# board__tzen.net
KiCad netlist of a schematic drawn in EAGLE
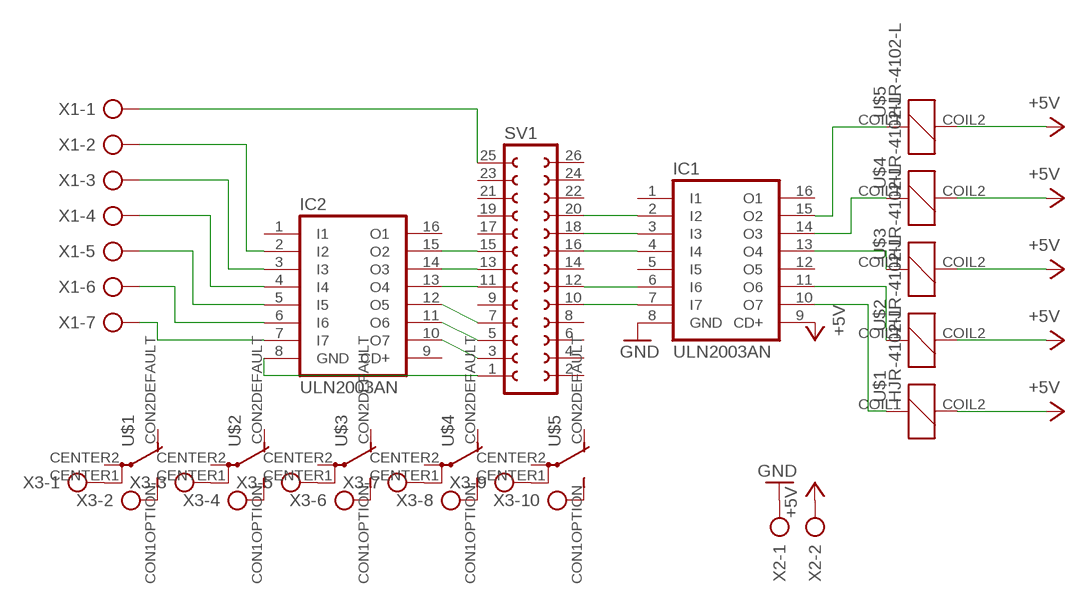
[diagram p0: schematic, sheet 1]

(export (version "E")
  (design (tool "Eeschema 10.0.6"))
  (components
    (comp (ref "IC1")
      (value "ULN2003AN")
      (footprint "eagle-import:DIL16")
      (libsource (lib "eagle-import") (part "ULN2003AN"))
    )
    (comp (ref "IC2")
      (value "ULN2003AN")
      (footprint "eagle-import:DIL16")
      (libsource (lib "eagle-import") (part "ULN2003AN"))
    )
    (comp (ref "SV1")
      (value "FE13-2")
      (footprint "eagle-import:FE13-2")
      (libsource (lib "eagle-import") (part "FE13-2"))
    )
    (comp (ref "U$1")
      (value "HJR-4102-L")
      (footprint "eagle-import:HJR4102")
      (libsource (lib "eagle-import") (part "HJR-4102-L"))
    )
    (comp (ref "U$2")
      (value "HJR-4102-L")
      (footprint "eagle-import:HJR4102")
      (libsource (lib "eagle-import") (part "HJR-4102-L"))
    )
    (comp (ref "U$3")
      (value "HJR-4102-L")
      (footprint "eagle-import:HJR4102")
      (libsource (lib "eagle-import") (part "HJR-4102-L"))
    )
    (comp (ref "U$4")
      (value "HJR-4102-L")
      (footprint "eagle-import:HJR4102")
      (libsource (lib "eagle-import") (part "HJR-4102-L"))
    )
    (comp (ref "U$5")
      (value "HJR-4102-L")
      (footprint "eagle-import:HJR4102")
      (libsource (lib "eagle-import") (part "HJR-4102-L"))
    )
    (comp (ref "X1")
      (value "AK500/7")
      (footprint "eagle-import:AK500_7")
      (libsource (lib "eagle-import") (part "AK500/7"))
    )
    (comp (ref "X2")
      (value "AK500/2")
      (footprint "eagle-import:AK500_2")
      (libsource (lib "eagle-import") (part "AK500/2"))
    )
    (comp (ref "X3")
      (value "AK500/10")
      (footprint "eagle-import:AK500_10")
      (libsource (lib "eagle-import") (part "AK500/10"))
    )
  )
  (nets
    (net (code "1") (name "+5V") (class "Default")
      (node (ref "IC1") (pin "9") (pinfunction "CD+_9") (pintype "passive"))
      (node (ref "U$1") (pin "COIL2") (pinfunction "2_COIL2") (pintype "passive"))
      (node (ref "U$2") (pin "COIL2") (pinfunction "2_COIL2") (pintype "passive"))
      (node (ref "U$3") (pin "COIL2") (pinfunction "2_COIL2") (pintype "passive"))
      (node (ref "U$4") (pin "COIL2") (pinfunction "2_COIL2") (pintype "passive"))
      (node (ref "U$5") (pin "COIL2") (pinfunction "2_COIL2") (pintype "passive"))
      (node (ref "X2") (pin "2") (pinfunction "KL_2") (pintype "passive"))
    )
    (net (code "2") (name "GND") (class "Default")
      (node (ref "IC1") (pin "8") (pinfunction "GND_8") (pintype "power_in"))
      (node (ref "X2") (pin "1") (pinfunction "KL_1") (pintype "passive"))
    )
    (net (code "3") (name "Net-(IC1-I2)") (class "Default")
      (node (ref "IC1") (pin "2") (pinfunction "I2_2") (pintype "input"))
      (node (ref "SV1") (pin "20") (pinfunction "20_20") (pintype "passive"))
    )
    (net (code "4") (name "Net-(IC1-I3)") (class "Default")
      (node (ref "IC1") (pin "3") (pinfunction "I3_3") (pintype "input"))
      (node (ref "SV1") (pin "18") (pinfunction "18_18") (pintype "passive"))
    )
    (net (code "5") (name "Net-(IC1-I4)") (class "Default")
      (node (ref "IC1") (pin "4") (pinfunction "I4_4") (pintype "input"))
      (node (ref "SV1") (pin "16") (pinfunction "16_16") (pintype "passive"))
    )
    (net (code "6") (name "Net-(IC1-I6)") (class "Default")
      (node (ref "IC1") (pin "6") (pinfunction "I6_6") (pintype "input"))
      (node (ref "SV1") (pin "12") (pinfunction "12_12") (pintype "passive"))
    )
    (net (code "7") (name "Net-(IC1-I7)") (class "Default")
      (node (ref "IC1") (pin "7") (pinfunction "I7_7") (pintype "input"))
      (node (ref "SV1") (pin "10") (pinfunction "10_10") (pintype "passive"))
    )
    (net (code "8") (name "Net-(IC1-O2)") (class "Default")
      (node (ref "IC1") (pin "15") (pinfunction "O2_15") (pintype "open_collector"))
      (node (ref "U$5") (pin "COIL1") (pinfunction "1_COIL1") (pintype "passive"))
    )
    (net (code "9") (name "Net-(IC1-O3)") (class "Default")
      (node (ref "IC1") (pin "14") (pinfunction "O3_14") (pintype "open_collector"))
      (node (ref "U$4") (pin "COIL1") (pinfunction "1_COIL1") (pintype "passive"))
    )
    (net (code "10") (name "Net-(IC1-O4)") (class "Default")
      (node (ref "IC1") (pin "13") (pinfunction "O4_13") (pintype "open_collector"))
      (node (ref "U$3") (pin "COIL1") (pinfunction "1_COIL1") (pintype "passive"))
    )
    (net (code "11") (name "Net-(IC1-O6)") (class "Default")
      (node (ref "IC1") (pin "11") (pinfunction "O6_11") (pintype "open_collector"))
      (node (ref "U$2") (pin "COIL1") (pinfunction "1_COIL1") (pintype "passive"))
    )
    (net (code "12") (name "Net-(IC1-O7)") (class "Default")
      (node (ref "IC1") (pin "10") (pinfunction "O7_10") (pintype "open_collector"))
      (node (ref "U$1") (pin "COIL1") (pinfunction "1_COIL1") (pintype "passive"))
    )
    (net (code "13") (name "Net-(IC2-GND)") (class "Default")
      (node (ref "IC2") (pin "8") (pinfunction "GND_8") (pintype "power_in"))
      (node (ref "SV1") (pin "1") (pinfunction "1_1") (pintype "passive"))
    )
    (net (code "14") (name "Net-(IC2-I2)") (class "Default")
      (node (ref "IC2") (pin "2") (pinfunction "I2_2") (pintype "input"))
      (node (ref "X1") (pin "2") (pinfunction "KL_2") (pintype "passive"))
    )
    (net (code "15") (name "Net-(IC2-I3)") (class "Default")
      (node (ref "IC2") (pin "3") (pinfunction "I3_3") (pintype "input"))
      (node (ref "X1") (pin "3") (pinfunction "KL_3") (pintype "passive"))
    )
    (net (code "16") (name "Net-(IC2-I4)") (class "Default")
      (node (ref "IC2") (pin "4") (pinfunction "I4_4") (pintype "input"))
      (node (ref "X1") (pin "4") (pinfunction "KL_4") (pintype "passive"))
    )
    (net (code "17") (name "Net-(IC2-I5)") (class "Default")
      (node (ref "IC2") (pin "5") (pinfunction "I5_5") (pintype "input"))
      (node (ref "X1") (pin "5") (pinfunction "KL_5") (pintype "passive"))
    )
    (net (code "18") (name "Net-(IC2-I6)") (class "Default")
      (node (ref "IC2") (pin "6") (pinfunction "I6_6") (pintype "input"))
      (node (ref "X1") (pin "6") (pinfunction "KL_6") (pintype "passive"))
    )
    (net (code "19") (name "Net-(IC2-I7)") (class "Default")
      (node (ref "IC2") (pin "7") (pinfunction "I7_7") (pintype "input"))
      (node (ref "X1") (pin "7") (pinfunction "KL_7") (pintype "passive"))
    )
    (net (code "20") (name "Net-(IC2-O2)") (class "Default")
      (node (ref "IC2") (pin "15") (pinfunction "O2_15") (pintype "open_collector"))
      (node (ref "SV1") (pin "15") (pinfunction "15_15") (pintype "passive"))
    )
    (net (code "21") (name "Net-(IC2-O3)") (class "Default")
      (node (ref "IC2") (pin "14") (pinfunction "O3_14") (pintype "open_collector"))
      (node (ref "SV1") (pin "13") (pinfunction "13_13") (pintype "passive"))
    )
    (net (code "22") (name "Net-(IC2-O4)") (class "Default")
      (node (ref "IC2") (pin "13") (pinfunction "O4_13") (pintype "open_collector"))
      (node (ref "SV1") (pin "11") (pinfunction "11_11") (pintype "passive"))
    )
    (net (code "23") (name "Net-(IC2-O5)") (class "Default")
      (node (ref "IC2") (pin "12") (pinfunction "O5_12") (pintype "open_collector"))
      (node (ref "SV1") (pin "7") (pinfunction "7_7") (pintype "passive"))
    )
    (net (code "24") (name "Net-(IC2-O6)") (class "Default")
      (node (ref "IC2") (pin "11") (pinfunction "O6_11") (pintype "open_collector"))
      (node (ref "SV1") (pin "5") (pinfunction "5_5") (pintype "passive"))
    )
    (net (code "25") (name "Net-(IC2-O7)") (class "Default")
      (node (ref "IC2") (pin "10") (pinfunction "O7_10") (pintype "open_collector"))
      (node (ref "SV1") (pin "3") (pinfunction "3_3") (pintype "passive"))
    )
    (net (code "26") (name "Net-(U$1B-S)") (class "Default")
      (node (ref "U$1") (pin "CON1OPTION") (pinfunction "S_CON1OPTION") (pintype "passive"))
      (node (ref "X3") (pin "2") (pinfunction "KL_2") (pintype "passive"))
    )
    (net (code "27") (name "Net-(U$2B-S)") (class "Default")
      (node (ref "U$2") (pin "CON1OPTION") (pinfunction "S_CON1OPTION") (pintype "passive"))
      (node (ref "X3") (pin "4") (pinfunction "KL_4") (pintype "passive"))
    )
    (net (code "28") (name "Net-(U$3B-S)") (class "Default")
      (node (ref "U$3") (pin "CON1OPTION") (pinfunction "S_CON1OPTION") (pintype "passive"))
      (node (ref "X3") (pin "6") (pinfunction "KL_6") (pintype "passive"))
    )
    (net (code "29") (name "Net-(U$4B-S)") (class "Default")
      (node (ref "U$4") (pin "CON1OPTION") (pinfunction "S_CON1OPTION") (pintype "passive"))
      (node (ref "X3") (pin "8") (pinfunction "KL_8") (pintype "passive"))
    )
    (net (code "30") (name "Net-(U$5B-S)") (class "Default")
      (node (ref "U$5") (pin "CON1OPTION") (pinfunction "S_CON1OPTION") (pintype "passive"))
      (node (ref "X3") (pin "10") (pinfunction "KL_10") (pintype "passive"))
    )
    (net (code "31") (name "Net-(X1A-KL)") (class "Default")
      (node (ref "SV1") (pin "25") (pinfunction "25_25") (pintype "passive"))
      (node (ref "X1") (pin "1") (pinfunction "KL_1") (pintype "passive"))
    )
    (net (code "32") (name "Net-(X3A-KL)") (class "Default")
      (node (ref "U$1") (pin "CENTER1") (pinfunction "P_CENTER1") (pintype "passive"))
      (node (ref "X3") (pin "1") (pinfunction "KL_1") (pintype "passive"))
    )
    (net (code "33") (name "Net-(X3D-KL)") (class "Default")
      (node (ref "U$2") (pin "CENTER1") (pinfunction "P_CENTER1") (pintype "passive"))
      (node (ref "X3") (pin "3") (pinfunction "KL_3") (pintype "passive"))
    )
    (net (code "34") (name "Net-(X3F-KL)") (class "Default")
      (node (ref "U$3") (pin "CENTER1") (pinfunction "P_CENTER1") (pintype "passive"))
      (node (ref "X3") (pin "5") (pinfunction "KL_5") (pintype "passive"))
    )
    (net (code "35") (name "Net-(X3H-KL)") (class "Default")
      (node (ref "U$4") (pin "CENTER1") (pinfunction "P_CENTER1") (pintype "passive"))
      (node (ref "X3") (pin "7") (pinfunction "KL_7") (pintype "passive"))
    )
    (net (code "36") (name "Net-(X3J-KL)") (class "Default")
      (node (ref "U$5") (pin "CENTER1") (pinfunction "P_CENTER1") (pintype "passive"))
      (node (ref "X3") (pin "9") (pinfunction "KL_9") (pintype "passive"))
    )
    (net (code "37") (name "unconnected-(IC1-I1-Pad1)") (class "Default")
      (node (ref "IC1") (pin "1") (pinfunction "I1_1") (pintype "input"))
    )
    (net (code "38") (name "unconnected-(IC1-I5-Pad5)") (class "Default")
      (node (ref "IC1") (pin "5") (pinfunction "I5_5") (pintype "input"))
    )
    (net (code "39") (name "unconnected-(IC1-O1-Pad16)") (class "Default")
      (node (ref "IC1") (pin "16") (pinfunction "O1_16") (pintype "open_collector"))
    )
    (net (code "40") (name "unconnected-(IC1-O5-Pad12)") (class "Default")
      (node (ref "IC1") (pin "12") (pinfunction "O5_12") (pintype "open_collector"))
    )
    (net (code "41") (name "unconnected-(IC2-CD+-Pad9)") (class "Default")
      (node (ref "IC2") (pin "9") (pinfunction "CD+_9") (pintype "passive"))
    )
    (net (code "42") (name "unconnected-(IC2-I1-Pad1)") (class "Default")
      (node (ref "IC2") (pin "1") (pinfunction "I1_1") (pintype "input"))
    )
    (net (code "43") (name "unconnected-(IC2-O1-Pad16)") (class "Default")
      (node (ref "IC2") (pin "16") (pinfunction "O1_16") (pintype "open_collector"))
    )
    (net (code "44") (name "unconnected-(SV1-Pad2)") (class "Default")
      (node (ref "SV1") (pin "2") (pinfunction "2_2") (pintype "passive"))
    )
    (net (code "45") (name "unconnected-(SV1-Pad4)") (class "Default")
      (node (ref "SV1") (pin "4") (pinfunction "4_4") (pintype "passive"))
    )
    (net (code "46") (name "unconnected-(SV1-Pad6)") (class "Default")
      (node (ref "SV1") (pin "6") (pinfunction "6_6") (pintype "passive"))
    )
    (net (code "47") (name "unconnected-(SV1-Pad8)") (class "Default")
      (node (ref "SV1") (pin "8") (pinfunction "8_8") (pintype "passive"))
    )
    (net (code "48") (name "unconnected-(SV1-Pad9)") (class "Default")
      (node (ref "SV1") (pin "9") (pinfunction "9_9") (pintype "passive"))
    )
    (net (code "49") (name "unconnected-(SV1-Pad14)") (class "Default")
      (node (ref "SV1") (pin "14") (pinfunction "14_14") (pintype "passive"))
    )
    (net (code "50") (name "unconnected-(SV1-Pad17)") (class "Default")
      (node (ref "SV1") (pin "17") (pinfunction "17_17") (pintype "passive"))
    )
    (net (code "51") (name "unconnected-(SV1-Pad19)") (class "Default")
      (node (ref "SV1") (pin "19") (pinfunction "19_19") (pintype "passive"))
    )
    (net (code "52") (name "unconnected-(SV1-Pad21)") (class "Default")
      (node (ref "SV1") (pin "21") (pinfunction "21_21") (pintype "passive"))
    )
    (net (code "53") (name "unconnected-(SV1-Pad22)") (class "Default")
      (node (ref "SV1") (pin "22") (pinfunction "22_22") (pintype "passive"))
    )
    (net (code "54") (name "unconnected-(SV1-Pad23)") (class "Default")
      (node (ref "SV1") (pin "23") (pinfunction "23_23") (pintype "passive"))
    )
    (net (code "55") (name "unconnected-(SV1-Pad24)") (class "Default")
      (node (ref "SV1") (pin "24") (pinfunction "24_24") (pintype "passive"))
    )
    (net (code "56") (name "unconnected-(SV1-Pad26)") (class "Default")
      (node (ref "SV1") (pin "26") (pinfunction "26_26") (pintype "passive"))
    )
    (net (code "57") (name "unconnected-(U$1B-O-PadCON2DEFAULT)") (class "Default")
      (node (ref "U$1") (pin "CON2DEFAULT") (pinfunction "O_CON2DEFAULT") (pintype "passive"))
    )
    (net (code "58") (name "unconnected-(U$1B-P-PadCENTER2)") (class "Default")
      (node (ref "U$1") (pin "CENTER2") (pinfunction "P_CENTER2") (pintype "passive"))
    )
    (net (code "59") (name "unconnected-(U$2B-O-PadCON2DEFAULT)") (class "Default")
      (node (ref "U$2") (pin "CON2DEFAULT") (pinfunction "O_CON2DEFAULT") (pintype "passive"))
    )
    (net (code "60") (name "unconnected-(U$2B-P-PadCENTER2)") (class "Default")
      (node (ref "U$2") (pin "CENTER2") (pinfunction "P_CENTER2") (pintype "passive"))
    )
    (net (code "61") (name "unconnected-(U$3B-O-PadCON2DEFAULT)") (class "Default")
      (node (ref "U$3") (pin "CON2DEFAULT") (pinfunction "O_CON2DEFAULT") (pintype "passive"))
    )
    (net (code "62") (name "unconnected-(U$3B-P-PadCENTER2)") (class "Default")
      (node (ref "U$3") (pin "CENTER2") (pinfunction "P_CENTER2") (pintype "passive"))
    )
    (net (code "63") (name "unconnected-(U$4B-O-PadCON2DEFAULT)") (class "Default")
      (node (ref "U$4") (pin "CON2DEFAULT") (pinfunction "O_CON2DEFAULT") (pintype "passive"))
    )
    (net (code "64") (name "unconnected-(U$4B-P-PadCENTER2)") (class "Default")
      (node (ref "U$4") (pin "CENTER2") (pinfunction "P_CENTER2") (pintype "passive"))
    )
    (net (code "65") (name "unconnected-(U$5B-O-PadCON2DEFAULT)") (class "Default")
      (node (ref "U$5") (pin "CON2DEFAULT") (pinfunction "O_CON2DEFAULT") (pintype "passive"))
    )
    (net (code "66") (name "unconnected-(U$5B-P-PadCENTER2)") (class "Default")
      (node (ref "U$5") (pin "CENTER2") (pinfunction "P_CENTER2") (pintype "passive"))
    )
  )
)
